# eeZeePower.net
KiCad netlist of a schematic drawn in EAGLE
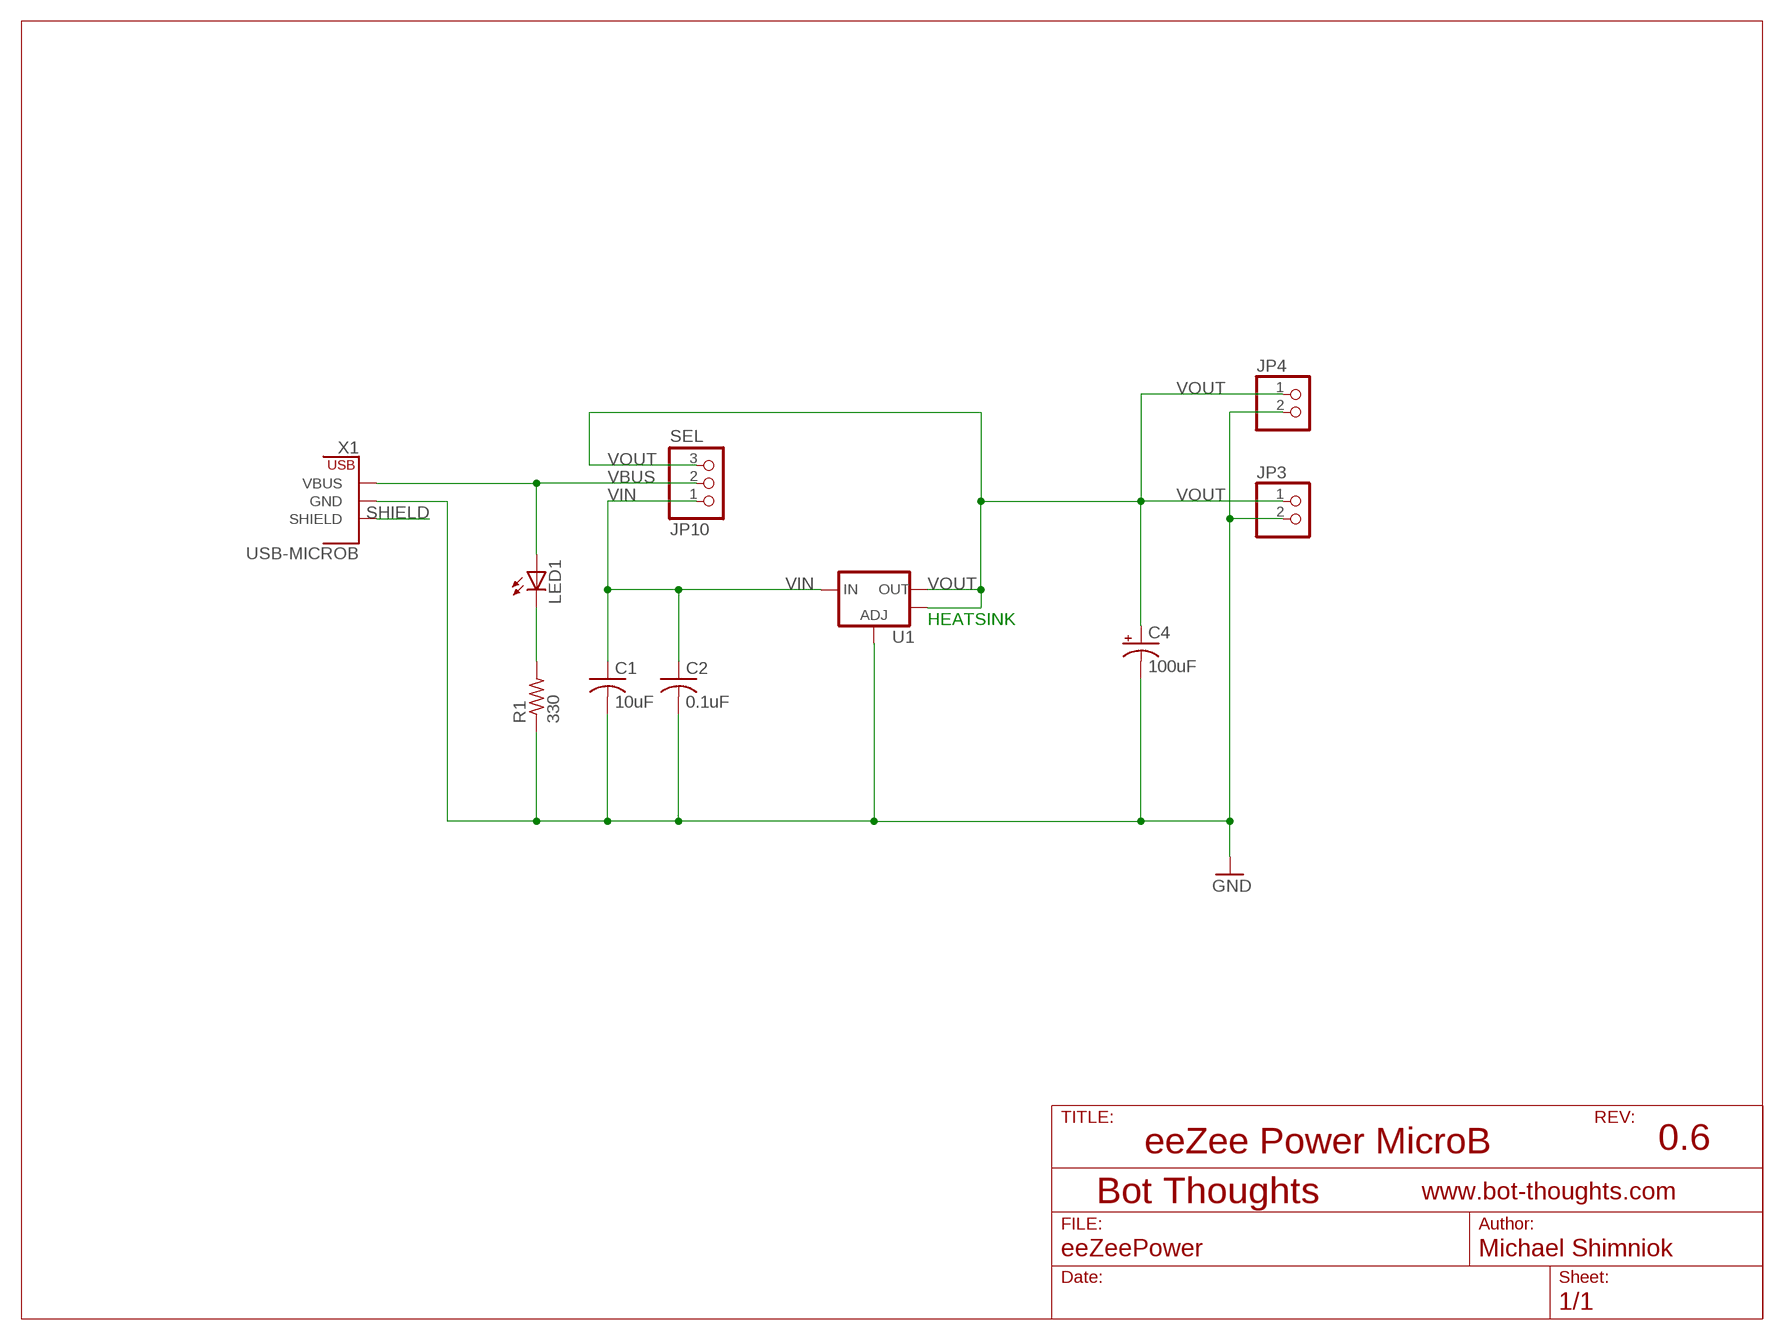
[diagram p0: schematic, sheet 1]

(export (version "E")
  (design (tool "Eeschema 10.0.6"))
  (components
    (comp (ref "C1")
      (value "10uF")
      (footprint "eagle-import:C1206")
      (libsource (lib "eagle-import") (part "C-USC1206"))
    )
    (comp (ref "C2")
      (value "0.1uF")
      (footprint "eagle-import:C0603")
      (libsource (lib "eagle-import") (part "C-USC0603"))
    )
    (comp (ref "C4")
      (value "100uF")
      (footprint "eagle-import:SMC_B")
      (libsource (lib "eagle-import") (part "CPOL-USSMCB"))
    )
    (comp (ref "JP3")
      (value "PINHD-1X02_2.54-S")
      (footprint "eagle-import:1X02-S")
      (libsource (lib "eagle-import") (part "PINHD-1X02_2.54-S"))
    )
    (comp (ref "JP4")
      (value "PINHD-1X02_2.54-S")
      (footprint "eagle-import:1X02-S")
      (libsource (lib "eagle-import") (part "PINHD-1X02_2.54-S"))
    )
    (comp (ref "JP10")
      (value "SEL")
      (footprint "eagle-import:1X03-S")
      (libsource (lib "eagle-import") (part "PINHD-1X03_2.54-S"))
    )
    (comp (ref "LED1")
      (value "LEDCHIPLED_1206")
      (footprint "eagle-import:CHIPLED_1206")
      (libsource (lib "eagle-import") (part "LEDCHIPLED_1206"))
    )
    (comp (ref "R1")
      (value "330")
      (footprint "eagle-import:R0603")
      (libsource (lib "eagle-import") (part "R-US_R0603"))
    )
    (comp (ref "U1")
      (value "V_REG_LM1117SOT223")
      (footprint "eagle-import:SOT223")
      (libsource (lib "eagle-import") (part "V_REG_LM1117SOT223"))
    )
    (comp (ref "X1")
      (value "USB-MICROB")
      (footprint "eagle-import:USB-MICROB-4")
      (libsource (lib "eagle-import") (part "USB_POWER-UB-4"))
    )
  )
  (nets
    (net (code "1") (name "/SHIELD") (class "Default")
      (node (ref "X1") (pin "SHIELD1") (pinfunction "SHIELD_SHIELD1") (pintype "bidirectional"))
      (node (ref "X1") (pin "SHIELD2") (pinfunction "SHIELD_SHIELD2") (pintype "bidirectional"))
      (node (ref "X1") (pin "SHIELD3") (pinfunction "SHIELD_SHIELD3") (pintype "bidirectional"))
      (node (ref "X1") (pin "SHIELD4") (pinfunction "SHIELD_SHIELD4") (pintype "bidirectional"))
      (node (ref "X1") (pin "SHIELD5") (pinfunction "SHIELD_SHIELD5") (pintype "bidirectional"))
      (node (ref "X1") (pin "SHIELD6") (pinfunction "SHIELD_SHIELD6") (pintype "bidirectional"))
    )
    (net (code "2") (name "/VBUS") (class "Default")
      (node (ref "JP10") (pin "2") (pinfunction "2_2") (pintype "passive"))
      (node (ref "LED1") (pin "A") (pinfunction "A_A") (pintype "passive"))
      (node (ref "X1") (pin "VBUS") (pinfunction "VBUS_VBUS") (pintype "power_in"))
    )
    (net (code "3") (name "/VIN") (class "Default")
      (node (ref "C1") (pin "1") (pinfunction "1_1") (pintype "passive"))
      (node (ref "C2") (pin "1") (pinfunction "1_1") (pintype "passive"))
      (node (ref "JP10") (pin "1") (pinfunction "1_1") (pintype "passive"))
      (node (ref "U1") (pin "3") (pinfunction "IN_3") (pintype "input"))
    )
    (net (code "4") (name "/VOUT") (class "Default")
      (node (ref "C4") (pin "+") (pinfunction "+_+") (pintype "passive"))
      (node (ref "JP10") (pin "3") (pinfunction "3_3") (pintype "passive"))
      (node (ref "JP3") (pin "1") (pinfunction "1_1") (pintype "passive"))
      (node (ref "JP4") (pin "1") (pinfunction "1_1") (pintype "passive"))
      (node (ref "U1") (pin "2") (pinfunction "OUT_2") (pintype "output"))
      (node (ref "U1") (pin "4") (pinfunction "OUT_4") (pintype "output"))
    )
    (net (code "5") (name "GND") (class "Default")
      (node (ref "C1") (pin "2") (pinfunction "2_2") (pintype "passive"))
      (node (ref "C2") (pin "2") (pinfunction "2_2") (pintype "passive"))
      (node (ref "C4") (pin "-") (pinfunction "-_-") (pintype "passive"))
      (node (ref "JP3") (pin "2") (pinfunction "2_2") (pintype "passive"))
      (node (ref "JP4") (pin "2") (pinfunction "2_2") (pintype "passive"))
      (node (ref "R1") (pin "1") (pinfunction "1_1") (pintype "passive"))
      (node (ref "U1") (pin "1") (pinfunction "ADJ_1") (pintype "input"))
      (node (ref "X1") (pin "GND") (pinfunction "GND_GND") (pintype "power_in"))
    )
    (net (code "6") (name "Net-(LED1-PadC)") (class "Default")
      (node (ref "LED1") (pin "C") (pinfunction "C_C") (pintype "passive"))
      (node (ref "R1") (pin "2") (pinfunction "2_2") (pintype "passive"))
    )
  )
)
